# jat501.net
KiCad netlist of a schematic drawn in EAGLE
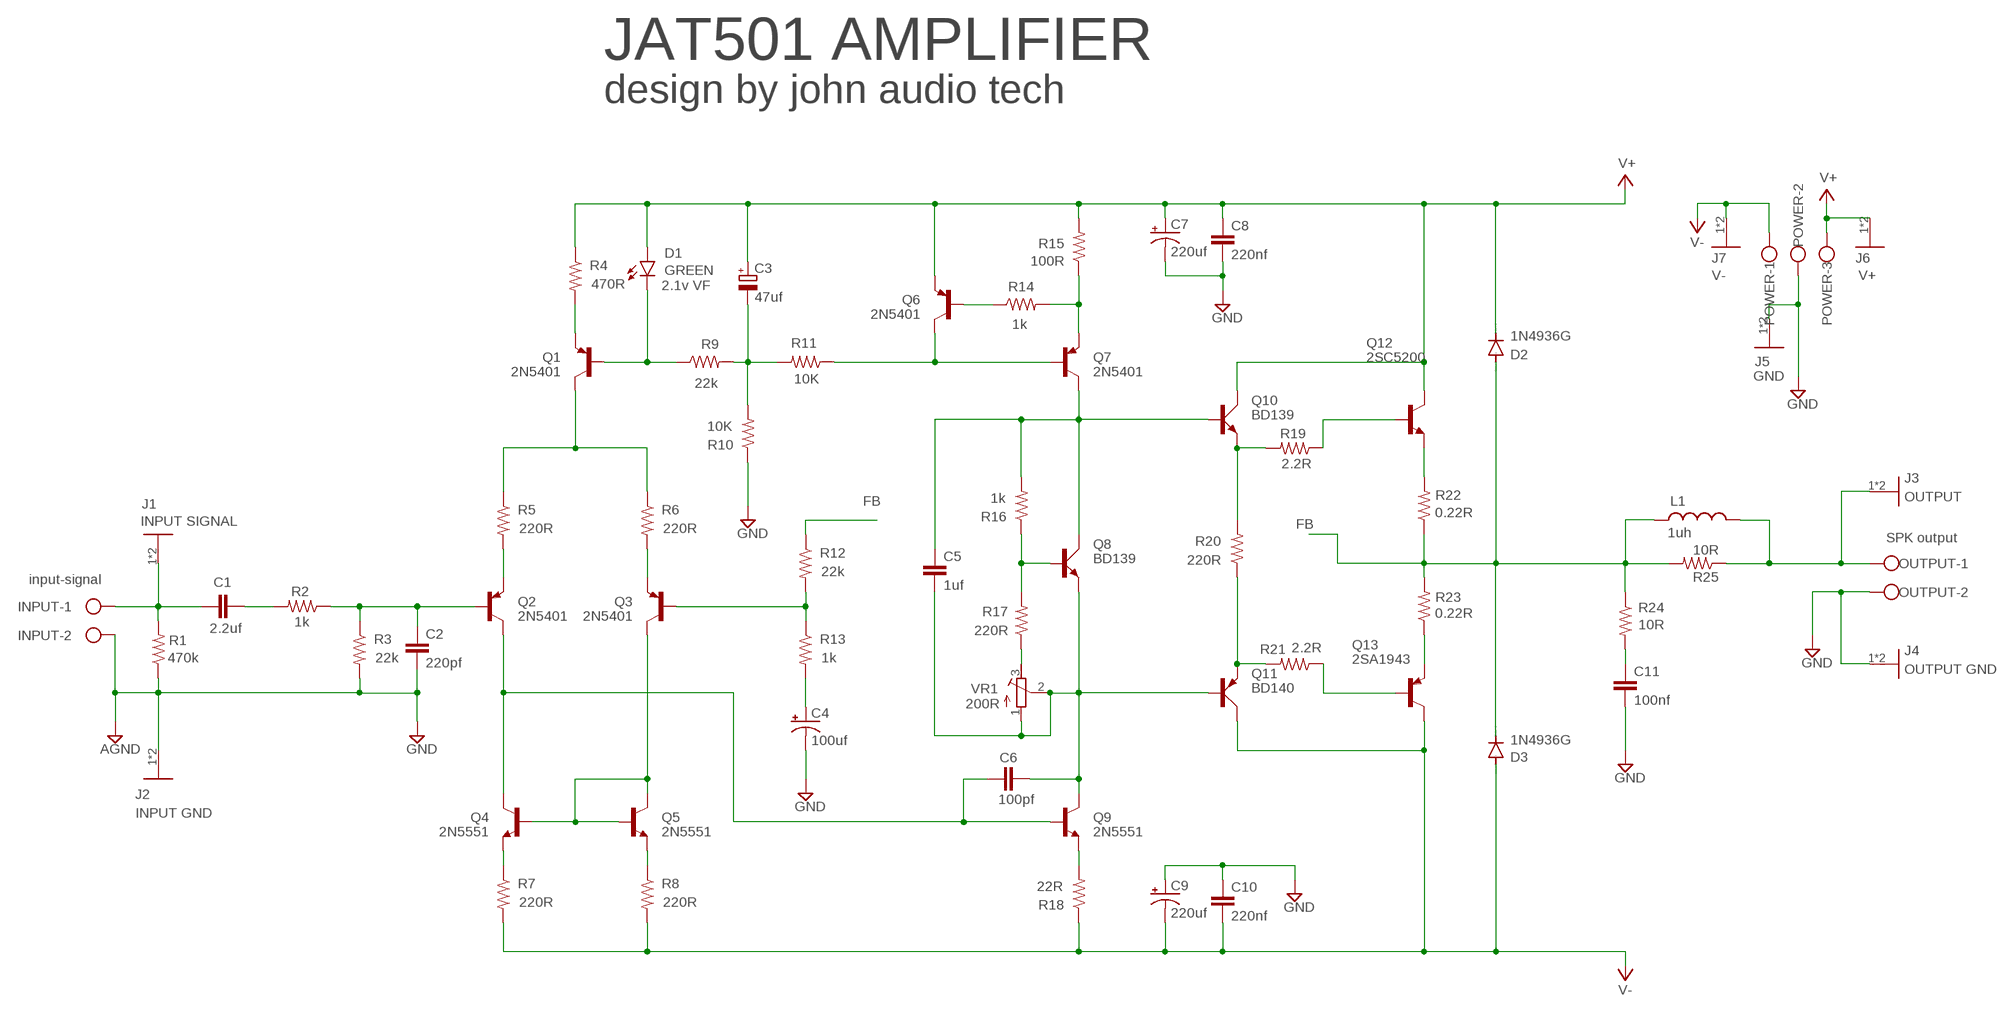
[diagram p0: schematic, sheet 1]

(export (version "E")
  (design (tool "Eeschema 10.0.6"))
  (components
    (comp (ref "C1")
      (value "2.2uf")
      (footprint "eagle-import:C150-072X183")
      (libsource (lib "eagle-import") (part "C-EU150-072X183"))
    )
    (comp (ref "C2")
      (value "220pf")
      (footprint "eagle-import:C050-035X075")
      (libsource (lib "eagle-import") (part "C-EU050-035X075"))
    )
    (comp (ref "C3")
      (value "47uf")
      (footprint "eagle-import:E5-8,5")
      (libsource (lib "eagle-import") (part "CPOL-EUE5-8.5"))
    )
    (comp (ref "C4")
      (value "100uf")
      (footprint "eagle-import:E5-13")
      (libsource (lib "eagle-import") (part "CPOL-USE5-13"))
    )
    (comp (ref "C5")
      (value "1uf")
      (footprint "eagle-import:C075-063X106")
      (libsource (lib "eagle-import") (part "C-EU075-063X106"))
    )
    (comp (ref "C6")
      (value "100pf")
      (footprint "eagle-import:C050-035X075")
      (libsource (lib "eagle-import") (part "C-EU050-035X075"))
    )
    (comp (ref "C7")
      (value "220uf")
      (footprint "eagle-import:E5-13")
      (libsource (lib "eagle-import") (part "CPOL-USE5-13"))
    )
    (comp (ref "C8")
      (value "220nf")
      (footprint "eagle-import:C050-075X075")
      (libsource (lib "eagle-import") (part "C-EU050-075X075"))
    )
    (comp (ref "C9")
      (value "220uf")
      (footprint "eagle-import:E5-13")
      (libsource (lib "eagle-import") (part "CPOL-USE5-13"))
    )
    (comp (ref "C10")
      (value "220nf")
      (footprint "eagle-import:C050-075X075")
      (libsource (lib "eagle-import") (part "C-EU050-075X075"))
    )
    (comp (ref "C11")
      (value "100nf")
      (footprint "eagle-import:C050-075X075")
      (libsource (lib "eagle-import") (part "C-EU050-075X075"))
    )
    (comp (ref "D1")
      (value "GREEN")
      (footprint "eagle-import:LED_5MM-KIT")
      (libsource (lib "eagle-import") (part "LED5MM-KIT"))
    )
    (comp (ref "D2")
      (value "1N4936G")
      (footprint "eagle-import:DO41-10")
      (libsource (lib "eagle-import") (part "1N4933"))
    )
    (comp (ref "D3")
      (value "1N4936G")
      (footprint "eagle-import:DO41-10")
      (libsource (lib "eagle-import") (part "1N4933"))
    )
    (comp (ref "INPUT")
      (value "input-signal")
      (footprint "eagle-import:W237-102")
      (fields (field (name "MPN") "237-102"))
      (libsource (lib "eagle-import") (part "W237-102"))
    )
    (comp (ref "J1")
      (value "INPUT SIGNAL")
      (footprint "eagle-import:TE_1217861-1")
      (fields (field (name "COMMENT") "1217861-1") (field (name "MF") "TE Connectivity"))
      (libsource (lib "eagle-import") (part "1217861-1"))
    )
    (comp (ref "J2")
      (value "INPUT GND")
      (footprint "eagle-import:TE_1217861-1")
      (fields (field (name "COMMENT") "1217861-1") (field (name "MF") "TE Connectivity"))
      (libsource (lib "eagle-import") (part "1217861-1"))
    )
    (comp (ref "J3")
      (value "OUTPUT")
      (footprint "eagle-import:TE_1217861-1")
      (fields (field (name "COMMENT") "1217861-1") (field (name "MF") "TE Connectivity"))
      (libsource (lib "eagle-import") (part "1217861-1"))
    )
    (comp (ref "J4")
      (value "OUTPUT GND")
      (footprint "eagle-import:TE_1217861-1")
      (fields (field (name "COMMENT") "1217861-1") (field (name "MF") "TE Connectivity"))
      (libsource (lib "eagle-import") (part "1217861-1"))
    )
    (comp (ref "J5")
      (value "GND")
      (footprint "eagle-import:TE_1217861-1")
      (fields (field (name "COMMENT") "1217861-1") (field (name "MF") "TE Connectivity"))
      (libsource (lib "eagle-import") (part "1217861-1"))
    )
    (comp (ref "J6")
      (value "V+")
      (footprint "eagle-import:TE_1217861-1")
      (fields (field (name "COMMENT") "1217861-1") (field (name "MF") "TE Connectivity"))
      (libsource (lib "eagle-import") (part "1217861-1"))
    )
    (comp (ref "J7")
      (value "V-")
      (footprint "eagle-import:TE_1217861-1")
      (fields (field (name "COMMENT") "1217861-1") (field (name "MF") "TE Connectivity"))
      (libsource (lib "eagle-import") (part "1217861-1"))
    )
    (comp (ref "L1")
      (value "1uh")
      (footprint "eagle-import:TFI0510")
      (libsource (lib "eagle-import") (part "L-USTFI0510"))
    )
    (comp (ref "OUTPUT")
      (value "SPK output")
      (footprint "eagle-import:W237-102")
      (fields (field (name "MPN") "237-102"))
      (libsource (lib "eagle-import") (part "W237-102"))
    )
    (comp (ref "POWER")
      (value "W237-103")
      (footprint "eagle-import:W237-103")
      (fields (field (name "MPN") "237-103"))
      (libsource (lib "eagle-import") (part "W237-103"))
    )
    (comp (ref "Q1")
      (value "2N5401")
      (footprint "eagle-import:TO92-EBC")
      (libsource (lib "eagle-import") (part "2N5401"))
    )
    (comp (ref "Q2")
      (value "2N5401")
      (footprint "eagle-import:TO92-EBC")
      (libsource (lib "eagle-import") (part "2N5401"))
    )
    (comp (ref "Q3")
      (value "2N5401")
      (footprint "eagle-import:TO92-EBC")
      (libsource (lib "eagle-import") (part "2N5401"))
    )
    (comp (ref "Q4")
      (value "2N5551")
      (footprint "eagle-import:TO92-EBC")
      (libsource (lib "eagle-import") (part "2N5551"))
    )
    (comp (ref "Q5")
      (value "2N5551")
      (footprint "eagle-import:TO92-EBC")
      (libsource (lib "eagle-import") (part "2N5551"))
    )
    (comp (ref "Q6")
      (value "2N5401")
      (footprint "eagle-import:TO92-EBC")
      (libsource (lib "eagle-import") (part "2N5401"))
    )
    (comp (ref "Q7")
      (value "2N5401")
      (footprint "eagle-import:TO92-EBC")
      (libsource (lib "eagle-import") (part "2N5401"))
    )
    (comp (ref "Q8")
      (value "BD139")
      (footprint "eagle-import:TO126AV")
      (libsource (lib "eagle-import") (part "BD139"))
    )
    (comp (ref "Q9")
      (value "2N5551")
      (footprint "eagle-import:TO92-EBC")
      (libsource (lib "eagle-import") (part "2N5551"))
    )
    (comp (ref "Q10")
      (value "BD139")
      (footprint "eagle-import:TO126AV")
      (libsource (lib "eagle-import") (part "BD139"))
    )
    (comp (ref "Q11")
      (value "BD140")
      (footprint "eagle-import:TO126AV")
      (libsource (lib "eagle-import") (part "BD140"))
    )
    (comp (ref "Q12")
      (value "2SC5200")
      (footprint "eagle-import:TO-264")
      (libsource (lib "eagle-import") (part "2SC5200"))
    )
    (comp (ref "Q13")
      (value "2SA1943")
      (footprint "eagle-import:TO-264")
      (libsource (lib "eagle-import") (part "2SA1943"))
    )
    (comp (ref "R1")
      (value "470k")
      (footprint "eagle-import:0207_10")
      (libsource (lib "eagle-import") (part "R-US_0207/10"))
    )
    (comp (ref "R2")
      (value "1k")
      (footprint "eagle-import:0207_10")
      (libsource (lib "eagle-import") (part "R-US_0207/10"))
    )
    (comp (ref "R3")
      (value "22k")
      (footprint "eagle-import:0207_10")
      (libsource (lib "eagle-import") (part "R-US_0207/10"))
    )
    (comp (ref "R4")
      (value "470R")
      (footprint "eagle-import:0207_10")
      (libsource (lib "eagle-import") (part "R-US_0207/10"))
    )
    (comp (ref "R5")
      (value "220R")
      (footprint "eagle-import:0207_10")
      (libsource (lib "eagle-import") (part "R-US_0207/10"))
    )
    (comp (ref "R6")
      (value "220R")
      (footprint "eagle-import:0207_10")
      (libsource (lib "eagle-import") (part "R-US_0207/10"))
    )
    (comp (ref "R7")
      (value "220R")
      (footprint "eagle-import:0207_10")
      (libsource (lib "eagle-import") (part "R-US_0207/10"))
    )
    (comp (ref "R8")
      (value "220R")
      (footprint "eagle-import:0207_10")
      (libsource (lib "eagle-import") (part "R-US_0207/10"))
    )
    (comp (ref "R9")
      (value "22k")
      (footprint "eagle-import:0207_10")
      (libsource (lib "eagle-import") (part "R-US_0207/10"))
    )
    (comp (ref "R10")
      (value "10K")
      (footprint "eagle-import:0207_10")
      (libsource (lib "eagle-import") (part "R-US_0207/10"))
    )
    (comp (ref "R11")
      (value "10K")
      (footprint "eagle-import:0207_10")
      (libsource (lib "eagle-import") (part "R-US_0207/10"))
    )
    (comp (ref "R12")
      (value "22k")
      (footprint "eagle-import:0207_10")
      (libsource (lib "eagle-import") (part "R-US_0207/10"))
    )
    (comp (ref "R13")
      (value "1k")
      (footprint "eagle-import:0207_10")
      (libsource (lib "eagle-import") (part "R-US_0207/10"))
    )
    (comp (ref "R14")
      (value "1k")
      (footprint "eagle-import:0207_10")
      (libsource (lib "eagle-import") (part "R-US_0207/10"))
    )
    (comp (ref "R15")
      (value "100R")
      (footprint "eagle-import:0207_10")
      (libsource (lib "eagle-import") (part "R-US_0207/10"))
    )
    (comp (ref "R16")
      (value "1k")
      (footprint "eagle-import:0207_10")
      (libsource (lib "eagle-import") (part "R-US_0207/10"))
    )
    (comp (ref "R17")
      (value "220R")
      (footprint "eagle-import:0207_10")
      (libsource (lib "eagle-import") (part "R-US_0207/10"))
    )
    (comp (ref "R18")
      (value "22R")
      (footprint "eagle-import:0207_10")
      (libsource (lib "eagle-import") (part "R-US_0207/10"))
    )
    (comp (ref "R19")
      (value "2.2R")
      (footprint "eagle-import:0207_10")
      (libsource (lib "eagle-import") (part "R-US_0207/10"))
    )
    (comp (ref "R20")
      (value "220R")
      (footprint "eagle-import:0207_10")
      (libsource (lib "eagle-import") (part "R-US_0207/10"))
    )
    (comp (ref "R21")
      (value "2.2R")
      (footprint "eagle-import:0207_10")
      (libsource (lib "eagle-import") (part "R-US_0207/10"))
    )
    (comp (ref "R22")
      (value "0.22R")
      (footprint "eagle-import:0922_22")
      (libsource (lib "eagle-import") (part "R-US_0922/22"))
    )
    (comp (ref "R23")
      (value "0.22R")
      (footprint "eagle-import:0922_22")
      (libsource (lib "eagle-import") (part "R-US_0922/22"))
    )
    (comp (ref "R24")
      (value "10R")
      (footprint "eagle-import:0922_22")
      (libsource (lib "eagle-import") (part "R-US_0922/22"))
    )
    (comp (ref "R25")
      (value "10R")
      (footprint "eagle-import:0922_22")
      (libsource (lib "eagle-import") (part "R-US_0922/22"))
    )
    (comp (ref "VR1")
      (value "200R")
      (footprint "eagle-import:RTRIM64W")
      (libsource (lib "eagle-import") (part "R-TRIMM64W"))
    )
  )
  (nets
    (net (code "1") (name "/FB") (class "Default")
      (node (ref "D2") (pin "A") (pinfunction "A_A") (pintype "passive"))
      (node (ref "D3") (pin "C") (pinfunction "C_C") (pintype "passive"))
      (node (ref "L1") (pin "1") (pinfunction "1_1") (pintype "passive"))
      (node (ref "R12") (pin "1") (pinfunction "1_1") (pintype "passive"))
      (node (ref "R22") (pin "1") (pinfunction "1_1") (pintype "passive"))
      (node (ref "R23") (pin "2") (pinfunction "2_2") (pintype "passive"))
      (node (ref "R24") (pin "1") (pinfunction "1_1") (pintype "passive"))
      (node (ref "R25") (pin "2") (pinfunction "2_2") (pintype "passive"))
    )
    (net (code "2") (name "AGND") (class "Default")
      (node (ref "C10") (pin "1") (pinfunction "1_1") (pintype "passive"))
      (node (ref "C11") (pin "2") (pinfunction "2_2") (pintype "passive"))
      (node (ref "C2") (pin "2") (pinfunction "2_2") (pintype "passive"))
      (node (ref "C4") (pin "-") (pinfunction "-_-") (pintype "passive"))
      (node (ref "C7") (pin "-") (pinfunction "-_-") (pintype "passive"))
      (node (ref "C8") (pin "2") (pinfunction "2_2") (pintype "passive"))
      (node (ref "C9") (pin "+") (pinfunction "+_+") (pintype "passive"))
      (node (ref "INPUT") (pin "2") (pinfunction "KL_2") (pintype "passive"))
      (node (ref "J2") (pin "1") (pinfunction "1_1") (pintype "passive"))
      (node (ref "J2") (pin "2") (pinfunction "1_2") (pintype "passive"))
      (node (ref "J4") (pin "1") (pinfunction "1_1") (pintype "passive"))
      (node (ref "J4") (pin "2") (pinfunction "1_2") (pintype "passive"))
      (node (ref "J5") (pin "1") (pinfunction "1_1") (pintype "passive"))
      (node (ref "J5") (pin "2") (pinfunction "1_2") (pintype "passive"))
      (node (ref "OUTPUT") (pin "2") (pinfunction "KL_2") (pintype "passive"))
      (node (ref "POWER") (pin "2") (pinfunction "KL_2") (pintype "passive"))
      (node (ref "R1") (pin "1") (pinfunction "1_1") (pintype "passive"))
      (node (ref "R10") (pin "1") (pinfunction "1_1") (pintype "passive"))
      (node (ref "R3") (pin "2") (pinfunction "2_2") (pintype "passive"))
    )
    (net (code "3") (name "Net-(C1-Pad2)") (class "Default")
      (node (ref "C1") (pin "2") (pinfunction "2_2") (pintype "passive"))
      (node (ref "R2") (pin "2") (pinfunction "2_2") (pintype "passive"))
    )
    (net (code "4") (name "Net-(C2-Pad1)") (class "Default")
      (node (ref "C2") (pin "1") (pinfunction "1_1") (pintype "passive"))
      (node (ref "Q2") (pin "B") (pinfunction "B_B") (pintype "passive"))
      (node (ref "R2") (pin "1") (pinfunction "1_1") (pintype "passive"))
      (node (ref "R3") (pin "1") (pinfunction "1_1") (pintype "passive"))
    )
    (net (code "5") (name "Net-(C3-Pad-)") (class "Default")
      (node (ref "C3") (pin "-") (pinfunction "-_-") (pintype "passive"))
      (node (ref "R10") (pin "2") (pinfunction "2_2") (pintype "passive"))
      (node (ref "R11") (pin "2") (pinfunction "2_2") (pintype "passive"))
      (node (ref "R9") (pin "2") (pinfunction "2_2") (pintype "passive"))
    )
    (net (code "6") (name "Net-(C4-Pad+)") (class "Default")
      (node (ref "C4") (pin "+") (pinfunction "+_+") (pintype "passive"))
      (node (ref "R13") (pin "2") (pinfunction "2_2") (pintype "passive"))
    )
    (net (code "7") (name "Net-(C5-Pad1)") (class "Default")
      (node (ref "C5") (pin "1") (pinfunction "1_1") (pintype "passive"))
      (node (ref "Q10") (pin "B") (pinfunction "B_B") (pintype "passive"))
      (node (ref "Q7") (pin "C") (pinfunction "C_C") (pintype "passive"))
      (node (ref "Q8") (pin "C") (pinfunction "C_C") (pintype "passive"))
      (node (ref "R16") (pin "2") (pinfunction "2_2") (pintype "passive"))
    )
    (net (code "8") (name "Net-(C6-Pad2)") (class "Default")
      (node (ref "C6") (pin "2") (pinfunction "2_2") (pintype "passive"))
      (node (ref "Q2") (pin "C") (pinfunction "C_C") (pintype "passive"))
      (node (ref "Q4") (pin "C") (pinfunction "C_C") (pintype "passive"))
      (node (ref "Q9") (pin "B") (pinfunction "B_B") (pintype "passive"))
    )
    (net (code "9") (name "Net-(C11-Pad1)") (class "Default")
      (node (ref "C11") (pin "1") (pinfunction "1_1") (pintype "passive"))
      (node (ref "R24") (pin "2") (pinfunction "2_2") (pintype "passive"))
    )
    (net (code "10") (name "Net-(D1-C)") (class "Default")
      (node (ref "D1") (pin "K") (pinfunction "C_K") (pintype "passive"))
      (node (ref "Q1") (pin "B") (pinfunction "B_B") (pintype "passive"))
      (node (ref "R9") (pin "1") (pinfunction "1_1") (pintype "passive"))
    )
    (net (code "11") (name "Net-(INPUTA-KL)") (class "Default")
      (node (ref "C1") (pin "1") (pinfunction "1_1") (pintype "passive"))
      (node (ref "INPUT") (pin "1") (pinfunction "KL_1") (pintype "passive"))
      (node (ref "J1") (pin "1") (pinfunction "1_1") (pintype "passive"))
      (node (ref "J1") (pin "2") (pinfunction "1_2") (pintype "passive"))
      (node (ref "R1") (pin "2") (pinfunction "2_2") (pintype "passive"))
    )
    (net (code "12") (name "Net-(OUTPUTA-KL)") (class "Default")
      (node (ref "J3") (pin "1") (pinfunction "1_1") (pintype "passive"))
      (node (ref "J3") (pin "2") (pinfunction "1_2") (pintype "passive"))
      (node (ref "L1") (pin "2") (pinfunction "2_2") (pintype "passive"))
      (node (ref "OUTPUT") (pin "1") (pinfunction "KL_1") (pintype "passive"))
      (node (ref "R25") (pin "1") (pinfunction "1_1") (pintype "passive"))
    )
    (net (code "13") (name "Net-(Q1-PadC)") (class "Default")
      (node (ref "Q1") (pin "C") (pinfunction "C_C") (pintype "passive"))
      (node (ref "R5") (pin "1") (pinfunction "1_1") (pintype "passive"))
      (node (ref "R6") (pin "1") (pinfunction "1_1") (pintype "passive"))
    )
    (net (code "14") (name "Net-(Q1-PadE)") (class "Default")
      (node (ref "Q1") (pin "E") (pinfunction "E_E") (pintype "passive"))
      (node (ref "R4") (pin "2") (pinfunction "2_2") (pintype "passive"))
    )
    (net (code "15") (name "Net-(Q2-PadE)") (class "Default")
      (node (ref "Q2") (pin "E") (pinfunction "E_E") (pintype "passive"))
      (node (ref "R5") (pin "2") (pinfunction "2_2") (pintype "passive"))
    )
    (net (code "16") (name "Net-(Q3-PadB)") (class "Default")
      (node (ref "Q3") (pin "B") (pinfunction "B_B") (pintype "passive"))
      (node (ref "R12") (pin "2") (pinfunction "2_2") (pintype "passive"))
      (node (ref "R13") (pin "1") (pinfunction "1_1") (pintype "passive"))
    )
    (net (code "17") (name "Net-(Q3-PadC)") (class "Default")
      (node (ref "Q3") (pin "C") (pinfunction "C_C") (pintype "passive"))
      (node (ref "Q4") (pin "B") (pinfunction "B_B") (pintype "passive"))
      (node (ref "Q5") (pin "B") (pinfunction "B_B") (pintype "passive"))
      (node (ref "Q5") (pin "C") (pinfunction "C_C") (pintype "passive"))
    )
    (net (code "18") (name "Net-(Q3-PadE)") (class "Default")
      (node (ref "Q3") (pin "E") (pinfunction "E_E") (pintype "passive"))
      (node (ref "R6") (pin "2") (pinfunction "2_2") (pintype "passive"))
    )
    (net (code "19") (name "Net-(Q4-PadE)") (class "Default")
      (node (ref "Q4") (pin "E") (pinfunction "E_E") (pintype "passive"))
      (node (ref "R7") (pin "1") (pinfunction "1_1") (pintype "passive"))
    )
    (net (code "20") (name "Net-(Q5-PadE)") (class "Default")
      (node (ref "Q5") (pin "E") (pinfunction "E_E") (pintype "passive"))
      (node (ref "R8") (pin "1") (pinfunction "1_1") (pintype "passive"))
    )
    (net (code "21") (name "Net-(Q6-PadB)") (class "Default")
      (node (ref "Q6") (pin "B") (pinfunction "B_B") (pintype "passive"))
      (node (ref "R14") (pin "1") (pinfunction "1_1") (pintype "passive"))
    )
    (net (code "22") (name "Net-(Q6-PadC)") (class "Default")
      (node (ref "Q6") (pin "C") (pinfunction "C_C") (pintype "passive"))
      (node (ref "Q7") (pin "B") (pinfunction "B_B") (pintype "passive"))
      (node (ref "R11") (pin "1") (pinfunction "1_1") (pintype "passive"))
    )
    (net (code "23") (name "Net-(Q7-PadE)") (class "Default")
      (node (ref "Q7") (pin "E") (pinfunction "E_E") (pintype "passive"))
      (node (ref "R14") (pin "2") (pinfunction "2_2") (pintype "passive"))
      (node (ref "R15") (pin "1") (pinfunction "1_1") (pintype "passive"))
    )
    (net (code "24") (name "Net-(Q8-PadB)") (class "Default")
      (node (ref "Q8") (pin "B") (pinfunction "B_B") (pintype "passive"))
      (node (ref "R16") (pin "1") (pinfunction "1_1") (pintype "passive"))
      (node (ref "R17") (pin "2") (pinfunction "2_2") (pintype "passive"))
    )
    (net (code "25") (name "Net-(Q9-PadE)") (class "Default")
      (node (ref "Q9") (pin "E") (pinfunction "E_E") (pintype "passive"))
      (node (ref "R18") (pin "2") (pinfunction "2_2") (pintype "passive"))
    )
    (net (code "26") (name "Net-(Q10-PadE)") (class "Default")
      (node (ref "Q10") (pin "E") (pinfunction "E_E") (pintype "passive"))
      (node (ref "R19") (pin "2") (pinfunction "2_2") (pintype "passive"))
      (node (ref "R20") (pin "2") (pinfunction "2_2") (pintype "passive"))
    )
    (net (code "27") (name "Net-(Q11-PadE)") (class "Default")
      (node (ref "Q11") (pin "E") (pinfunction "E_E") (pintype "passive"))
      (node (ref "R20") (pin "1") (pinfunction "1_1") (pintype "passive"))
      (node (ref "R21") (pin "2") (pinfunction "2_2") (pintype "passive"))
    )
    (net (code "28") (name "Net-(Q12-PadB)") (class "Default")
      (node (ref "Q12") (pin "B") (pinfunction "B_B") (pintype "passive"))
      (node (ref "R19") (pin "1") (pinfunction "1_1") (pintype "passive"))
    )
    (net (code "29") (name "Net-(Q12-PadE)") (class "Default")
      (node (ref "Q12") (pin "E") (pinfunction "E_E") (pintype "passive"))
      (node (ref "R22") (pin "2") (pinfunction "2_2") (pintype "passive"))
    )
    (net (code "30") (name "Net-(Q13-PadB)") (class "Default")
      (node (ref "Q13") (pin "B") (pinfunction "B_B") (pintype "passive"))
      (node (ref "R21") (pin "1") (pinfunction "1_1") (pintype "passive"))
    )
    (net (code "31") (name "Net-(Q13-PadE)") (class "Default")
      (node (ref "Q13") (pin "E") (pinfunction "E_E") (pintype "passive"))
      (node (ref "R23") (pin "1") (pinfunction "1_1") (pintype "passive"))
    )
    (net (code "32") (name "Net-(VR1-A)") (class "Default")
      (node (ref "C5") (pin "2") (pinfunction "2_2") (pintype "passive"))
      (node (ref "C6") (pin "1") (pinfunction "1_1") (pintype "passive"))
      (node (ref "Q11") (pin "B") (pinfunction "B_B") (pintype "passive"))
      (node (ref "Q8") (pin "E") (pinfunction "E_E") (pintype "passive"))
      (node (ref "Q9") (pin "C") (pinfunction "C_C") (pintype "passive"))
      (node (ref "VR1") (pin "1") (pinfunction "A_1") (pintype "passive"))
      (node (ref "VR1") (pin "2") (pinfunction "S_2") (pintype "passive"))
    )
    (net (code "33") (name "Net-(VR1-E)") (class "Default")
      (node (ref "R17") (pin "1") (pinfunction "1_1") (pintype "passive"))
      (node (ref "VR1") (pin "3") (pinfunction "E_3") (pintype "passive"))
    )
    (net (code "34") (name "V+") (class "Default")
      (node (ref "C3") (pin "+") (pinfunction "+_+") (pintype "passive"))
      (node (ref "C7") (pin "+") (pinfunction "+_+") (pintype "passive"))
      (node (ref "C8") (pin "1") (pinfunction "1_1") (pintype "passive"))
      (node (ref "D1") (pin "A") (pinfunction "A_A") (pintype "passive"))
      (node (ref "D2") (pin "C") (pinfunction "C_C") (pintype "passive"))
      (node (ref "J6") (pin "1") (pinfunction "1_1") (pintype "passive"))
      (node (ref "J6") (pin "2") (pinfunction "1_2") (pintype "passive"))
      (node (ref "POWER") (pin "3") (pinfunction "KL_3") (pintype "passive"))
      (node (ref "Q10") (pin "C") (pinfunction "C_C") (pintype "passive"))
      (node (ref "Q12") (pin "C") (pinfunction "C_C") (pintype "passive"))
      (node (ref "Q6") (pin "E") (pinfunction "E_E") (pintype "passive"))
      (node (ref "R15") (pin "2") (pinfunction "2_2") (pintype "passive"))
      (node (ref "R4") (pin "1") (pinfunction "1_1") (pintype "passive"))
    )
    (net (code "35") (name "V-") (class "Default")
      (node (ref "C10") (pin "2") (pinfunction "2_2") (pintype "passive"))
      (node (ref "C9") (pin "-") (pinfunction "-_-") (pintype "passive"))
      (node (ref "D3") (pin "A") (pinfunction "A_A") (pintype "passive"))
      (node (ref "J7") (pin "1") (pinfunction "1_1") (pintype "passive"))
      (node (ref "J7") (pin "2") (pinfunction "1_2") (pintype "passive"))
      (node (ref "POWER") (pin "1") (pinfunction "KL_1") (pintype "passive"))
      (node (ref "Q11") (pin "C") (pinfunction "C_C") (pintype "passive"))
      (node (ref "Q13") (pin "C") (pinfunction "C_C") (pintype "passive"))
      (node (ref "R18") (pin "1") (pinfunction "1_1") (pintype "passive"))
      (node (ref "R7") (pin "2") (pinfunction "2_2") (pintype "passive"))
      (node (ref "R8") (pin "2") (pinfunction "2_2") (pintype "passive"))
    )
  )
)
